# RocketSenseV1.net
KiCad netlist of a schematic drawn in EAGLE
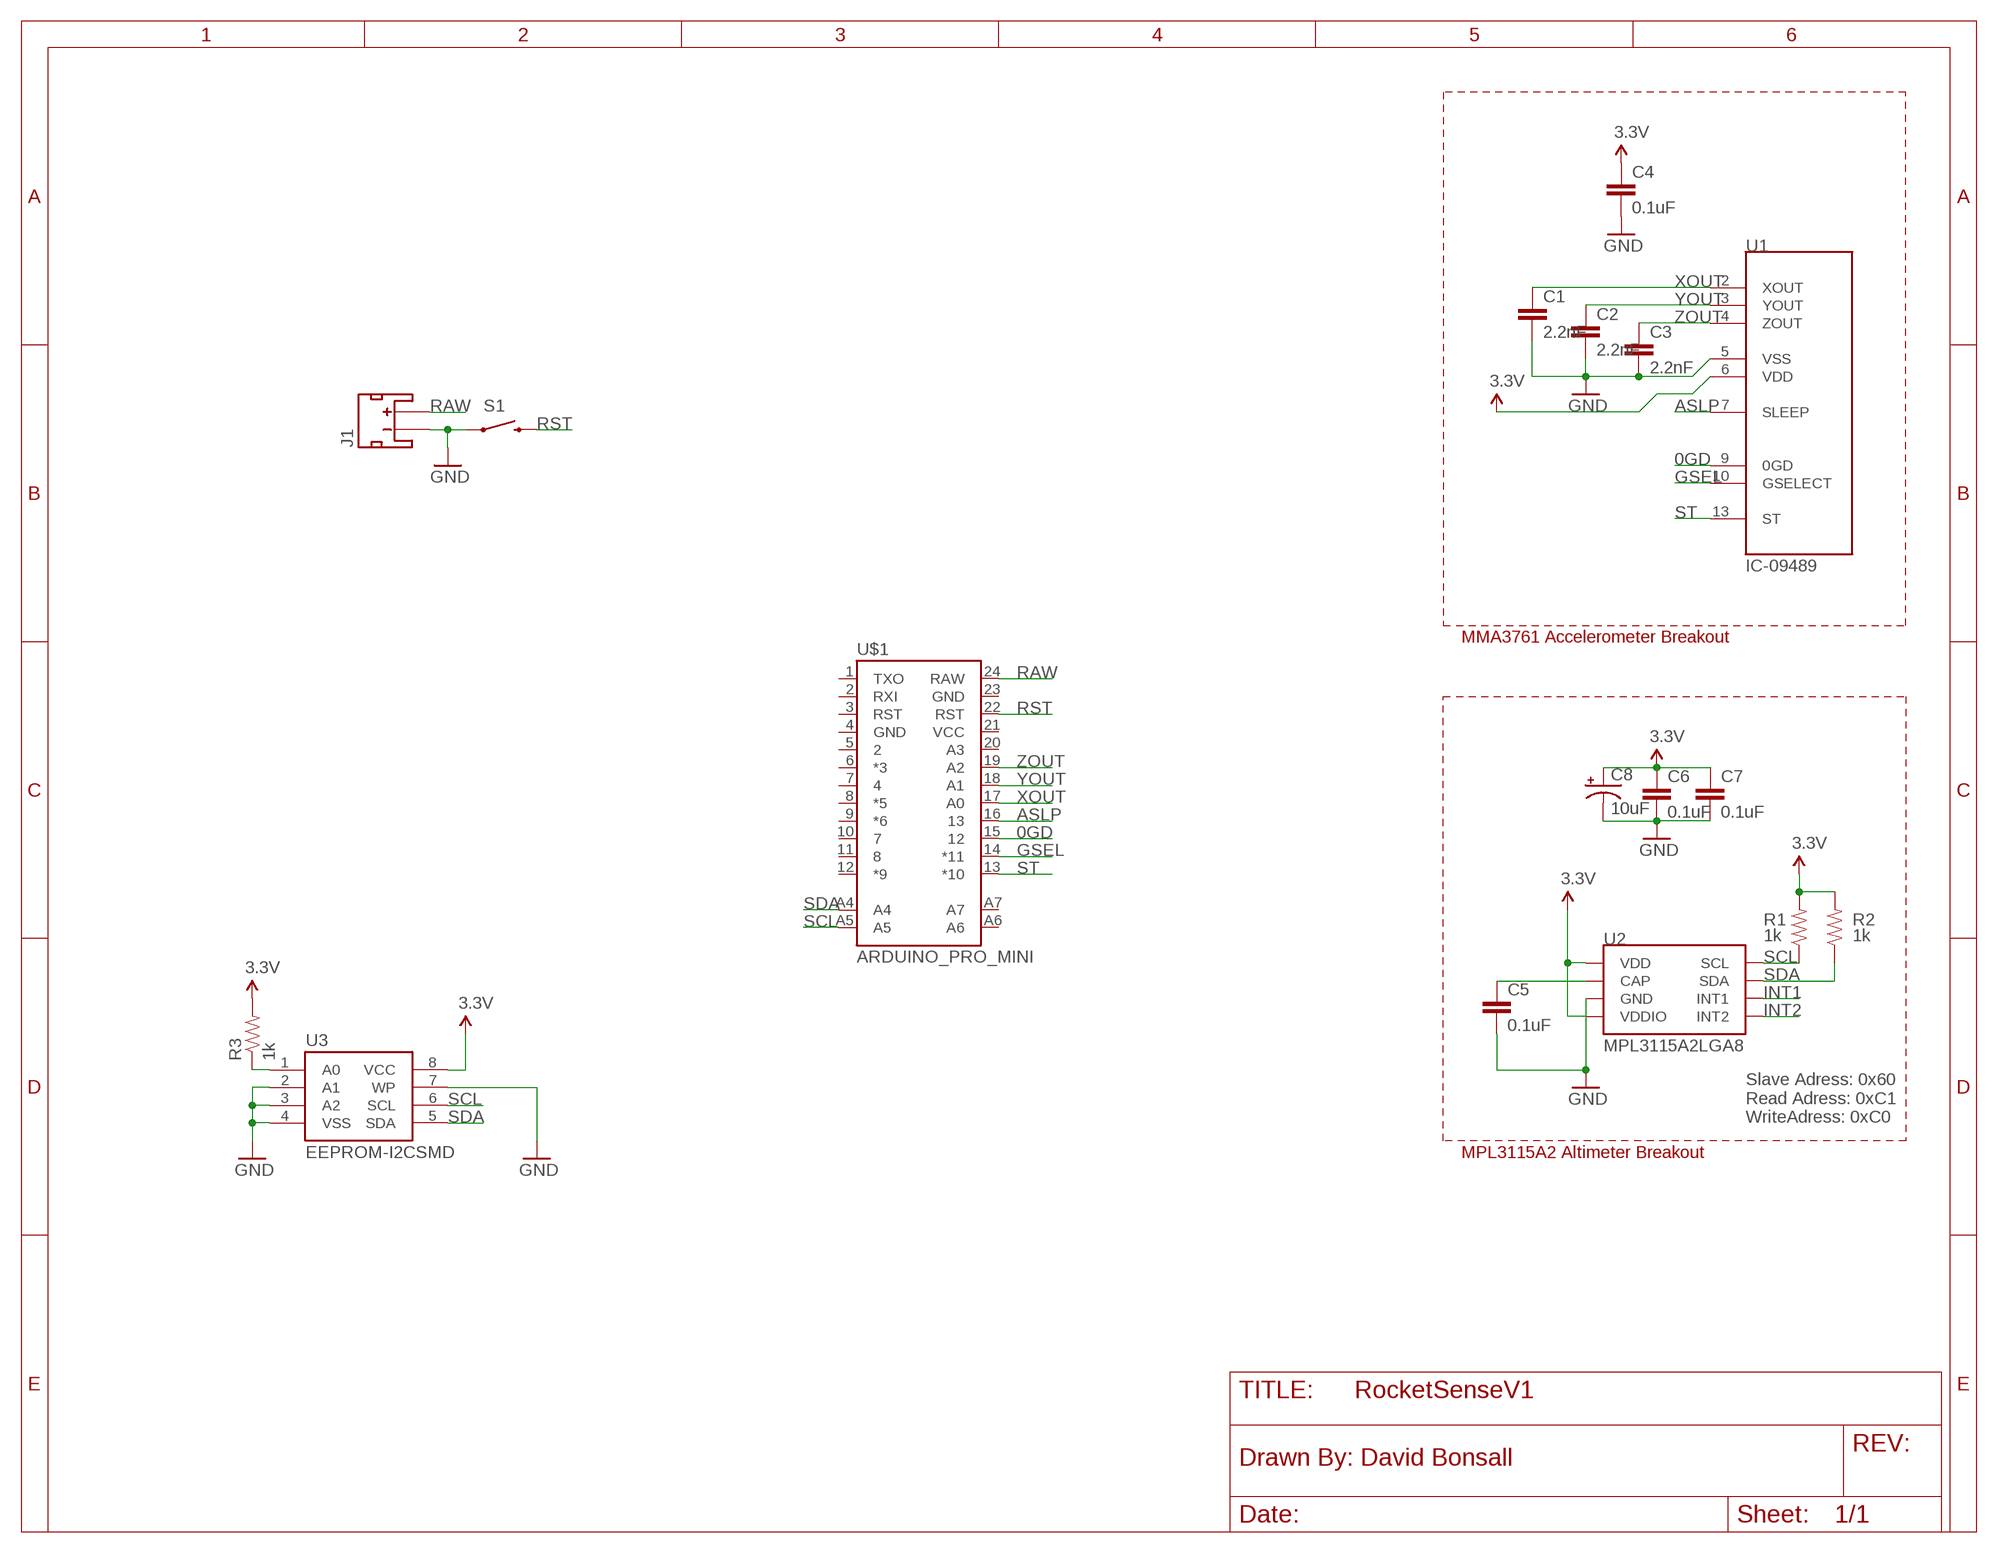
[diagram p0: schematic, sheet 1]

(export (version "E")
  (design (tool "Eeschema 10.0.6"))
  (components
    (comp (ref "C1")
      (value "2.2nF")
      (footprint "eagle-import:0603-CAP")
      (libsource (lib "eagle-import") (part "2.2NF/2200PF-50V-10%(0603)"))
    )
    (comp (ref "C2")
      (value "2.2nF")
      (footprint "eagle-import:0603-CAP")
      (libsource (lib "eagle-import") (part "2.2NF/2200PF-50V-10%(0603)"))
    )
    (comp (ref "C3")
      (value "2.2nF")
      (footprint "eagle-import:0603-CAP")
      (libsource (lib "eagle-import") (part "2.2NF/2200PF-50V-10%(0603)"))
    )
    (comp (ref "C4")
      (value "0.1uF")
      (footprint "eagle-import:0402-CAP")
      (libsource (lib "eagle-import") (part ".1UF-CER"))
    )
    (comp (ref "C5")
      (value "0.1uF")
      (footprint "eagle-import:0402-CAP")
      (libsource (lib "eagle-import") (part ".1UF-CER"))
    )
    (comp (ref "C6")
      (value "0.1uF")
      (footprint "eagle-import:0402-CAP")
      (libsource (lib "eagle-import") (part ".1UF-CER"))
    )
    (comp (ref "C7")
      (value "0.1uF")
      (footprint "eagle-import:0402-CAP")
      (libsource (lib "eagle-import") (part ".1UF-CER"))
    )
    (comp (ref "C8")
      (value "10uF")
      (footprint "eagle-import:EIA3216")
      (libsource (lib "eagle-import") (part "10UF-16V-10%(TANT)"))
    )
    (comp (ref "J1")
      (value "JST_2MM_MALE")
      (footprint "eagle-import:JST-2-SMD")
      (libsource (lib "eagle-import") (part "JST_2MM_MALE"))
    )
    (comp (ref "R1")
      (value "1k")
      (footprint "eagle-import:0603-RES")
      (libsource (lib "eagle-import") (part "1K-1%"))
    )
    (comp (ref "R2")
      (value "1k")
      (footprint "eagle-import:0603-RES")
      (libsource (lib "eagle-import") (part "1K-1%"))
    )
    (comp (ref "R3")
      (value "1k")
      (footprint "eagle-import:0603-RES")
      (libsource (lib "eagle-import") (part "1K-1%"))
    )
    (comp (ref "S1")
      (value "SWITCH-MOMENTARY-2-SMD-1101NE")
      (footprint "eagle-import:TACTILE-SWITCH-1101NE")
      (libsource (lib "eagle-import") (part "SWITCH-MOMENTARY-2-SMD-1101NE"))
    )
    (comp (ref "U$1")
      (value "ARDUINO_PRO_MINI")
      (footprint "eagle-import:ARDUINO_PRO_MINI")
      (libsource (lib "eagle-import") (part "ARDUINO_PRO_MINI"))
    )
    (comp (ref "U1")
      (value "IC-09489")
      (footprint "eagle-import:LGA14")
      (libsource (lib "eagle-import") (part "MMA7361"))
    )
    (comp (ref "U2")
      (value "MPL3115A2LGA8")
      (footprint "eagle-import:LGA8")
      (libsource (lib "eagle-import") (part "MPL3115A2LGA8"))
    )
    (comp (ref "U3")
      (value "EEPROM-I2CSMD")
      (footprint "eagle-import:SO08")
      (libsource (lib "eagle-import") (part "EEPROM-I2CSMD"))
    )
  )
  (nets
    (net (code "1") (name "/0GD") (class "Default")
      (node (ref "U$1") (pin "15") (pinfunction "12_15") (pintype "bidirectional"))
      (node (ref "U1") (pin "9") (pinfunction "0GD_9") (pintype "bidirectional"))
    )
    (net (code "2") (name "/ASLP") (class "Default")
      (node (ref "U$1") (pin "16") (pinfunction "13_16") (pintype "bidirectional"))
      (node (ref "U1") (pin "7") (pinfunction "SLEEP_7") (pintype "bidirectional"))
    )
    (net (code "3") (name "/GSEL") (class "Default")
      (node (ref "U$1") (pin "14") (pinfunction "*11_14") (pintype "bidirectional"))
      (node (ref "U1") (pin "10") (pinfunction "GSELECT_10") (pintype "bidirectional"))
    )
    (net (code "4") (name "/INT1") (class "Default")
      (node (ref "U2") (pin "6") (pinfunction "INT1_6") (pintype "output"))
    )
    (net (code "5") (name "/INT2") (class "Default")
      (node (ref "U2") (pin "5") (pinfunction "INT2_5") (pintype "output"))
    )
    (net (code "6") (name "/RAW") (class "Default")
      (node (ref "J1") (pin "2") (pinfunction "+_2") (pintype "bidirectional"))
      (node (ref "U$1") (pin "24") (pinfunction "RAW_24") (pintype "bidirectional"))
    )
    (net (code "7") (name "/RST") (class "Default")
      (node (ref "S1") (pin "P$2") (pinfunction "2_P$2") (pintype "passive"))
      (node (ref "U$1") (pin "22") (pinfunction "RST_22") (pintype "bidirectional"))
    )
    (net (code "8") (name "/SCL") (class "Default")
      (node (ref "R1") (pin "1") (pinfunction "1_1") (pintype "passive"))
      (node (ref "U$1") (pin "A5") (pinfunction "A5_A5") (pintype "bidirectional"))
      (node (ref "U2") (pin "8") (pinfunction "SCL_8") (pintype "bidirectional"))
      (node (ref "U3") (pin "6") (pinfunction "SCL_6") (pintype "bidirectional"))
    )
    (net (code "9") (name "/SDA") (class "Default")
      (node (ref "R2") (pin "1") (pinfunction "1_1") (pintype "passive"))
      (node (ref "U$1") (pin "A4") (pinfunction "A4_A4") (pintype "bidirectional"))
      (node (ref "U2") (pin "7") (pinfunction "SDA_7") (pintype "bidirectional"))
      (node (ref "U3") (pin "5") (pinfunction "SDA_5") (pintype "bidirectional"))
    )
    (net (code "10") (name "/ST") (class "Default")
      (node (ref "U$1") (pin "13") (pinfunction "*10_13") (pintype "bidirectional"))
      (node (ref "U1") (pin "13") (pinfunction "ST_13") (pintype "bidirectional"))
    )
    (net (code "11") (name "/XOUT") (class "Default")
      (node (ref "C1") (pin "1") (pinfunction "1_1") (pintype "passive"))
      (node (ref "U$1") (pin "17") (pinfunction "A0_17") (pintype "bidirectional"))
      (node (ref "U1") (pin "2") (pinfunction "XOUT_2") (pintype "bidirectional"))
    )
    (net (code "12") (name "/YOUT") (class "Default")
      (node (ref "C2") (pin "1") (pinfunction "1_1") (pintype "passive"))
      (node (ref "U$1") (pin "18") (pinfunction "A1_18") (pintype "bidirectional"))
      (node (ref "U1") (pin "3") (pinfunction "YOUT_3") (pintype "bidirectional"))
    )
    (net (code "13") (name "/ZOUT") (class "Default")
      (node (ref "C3") (pin "1") (pinfunction "1_1") (pintype "passive"))
      (node (ref "U$1") (pin "19") (pinfunction "A2_19") (pintype "bidirectional"))
      (node (ref "U1") (pin "4") (pinfunction "ZOUT_4") (pintype "bidirectional"))
    )
    (net (code "14") (name "3.3V") (class "Default")
      (node (ref "C4") (pin "1") (pinfunction "1_1") (pintype "passive"))
      (node (ref "C6") (pin "1") (pinfunction "1_1") (pintype "passive"))
      (node (ref "C7") (pin "1") (pinfunction "1_1") (pintype "passive"))
      (node (ref "C8") (pin "A") (pinfunction "+_A") (pintype "passive"))
      (node (ref "R1") (pin "2") (pinfunction "2_2") (pintype "passive"))
      (node (ref "R2") (pin "2") (pinfunction "2_2") (pintype "passive"))
      (node (ref "R3") (pin "2") (pinfunction "2_2") (pintype "passive"))
      (node (ref "U1") (pin "6") (pinfunction "VDD_6") (pintype "bidirectional"))
      (node (ref "U2") (pin "1") (pinfunction "VDD_1") (pintype "power_in"))
      (node (ref "U2") (pin "4") (pinfunction "VDDIO_4") (pintype "power_in"))
      (node (ref "U3") (pin "8") (pinfunction "VCC_8") (pintype "power_in"))
    )
    (net (code "15") (name "GND") (class "Default")
      (node (ref "C1") (pin "2") (pinfunction "2_2") (pintype "passive"))
      (node (ref "C2") (pin "2") (pinfunction "2_2") (pintype "passive"))
      (node (ref "C3") (pin "2") (pinfunction "2_2") (pintype "passive"))
      (node (ref "C4") (pin "2") (pinfunction "2_2") (pintype "passive"))
      (node (ref "C5") (pin "2") (pinfunction "2_2") (pintype "passive"))
      (node (ref "C6") (pin "2") (pinfunction "2_2") (pintype "passive"))
      (node (ref "C7") (pin "2") (pinfunction "2_2") (pintype "passive"))
      (node (ref "C8") (pin "C") (pinfunction "-_C") (pintype "passive"))
      (node (ref "J1") (pin "1") (pinfunction "-_1") (pintype "bidirectional"))
      (node (ref "S1") (pin "P$1") (pinfunction "1_P$1") (pintype "passive"))
      (node (ref "U1") (pin "5") (pinfunction "VSS_5") (pintype "bidirectional"))
      (node (ref "U2") (pin "3") (pinfunction "GND_3") (pintype "power_in"))
      (node (ref "U3") (pin "2") (pinfunction "A1_2") (pintype "bidirectional"))
      (node (ref "U3") (pin "3") (pinfunction "A2_3") (pintype "bidirectional"))
      (node (ref "U3") (pin "4") (pinfunction "VSS_4") (pintype "power_in"))
      (node (ref "U3") (pin "7") (pinfunction "WP_7") (pintype "bidirectional"))
    )
    (net (code "16") (name "Net-(U2-CAP)") (class "Default")
      (node (ref "C5") (pin "1") (pinfunction "1_1") (pintype "passive"))
      (node (ref "U2") (pin "2") (pinfunction "CAP_2") (pintype "power_in"))
    )
    (net (code "17") (name "Net-(U3-A0)") (class "Default")
      (node (ref "R3") (pin "1") (pinfunction "1_1") (pintype "passive"))
      (node (ref "U3") (pin "1") (pinfunction "A0_1") (pintype "bidirectional"))
    )
    (net (code "18") (name "unconnected-(J1-PAD1-PadNC1)") (class "Default")
      (node (ref "J1") (pin "NC1") (pinfunction "PAD1_NC1") (pintype "bidirectional"))
    )
    (net (code "19") (name "unconnected-(J1-PAD2-PadNC2)") (class "Default")
      (node (ref "J1") (pin "NC2") (pinfunction "PAD2_NC2") (pintype "bidirectional"))
    )
    (net (code "20") (name "unconnected-(U$1-*3-Pad6)") (class "Default")
      (node (ref "U$1") (pin "6") (pinfunction "*3_6") (pintype "bidirectional"))
    )
    (net (code "21") (name "unconnected-(U$1-*5-Pad8)") (class "Default")
      (node (ref "U$1") (pin "8") (pinfunction "*5_8") (pintype "bidirectional"))
    )
    (net (code "22") (name "unconnected-(U$1-*6-Pad9)") (class "Default")
      (node (ref "U$1") (pin "9") (pinfunction "*6_9") (pintype "bidirectional"))
    )
    (net (code "23") (name "unconnected-(U$1-*9-Pad12)") (class "Default")
      (node (ref "U$1") (pin "12") (pinfunction "*9_12") (pintype "bidirectional"))
    )
    (net (code "24") (name "unconnected-(U$1-2-Pad5)") (class "Default")
      (node (ref "U$1") (pin "5") (pinfunction "2_5") (pintype "bidirectional"))
    )
    (net (code "25") (name "unconnected-(U$1-4-Pad7)") (class "Default")
      (node (ref "U$1") (pin "7") (pinfunction "4_7") (pintype "bidirectional"))
    )
    (net (code "26") (name "unconnected-(U$1-7-Pad10)") (class "Default")
      (node (ref "U$1") (pin "10") (pinfunction "7_10") (pintype "bidirectional"))
    )
    (net (code "27") (name "unconnected-(U$1-8-Pad11)") (class "Default")
      (node (ref "U$1") (pin "11") (pinfunction "8_11") (pintype "bidirectional"))
    )
    (net (code "28") (name "unconnected-(U$1-A3-Pad20)") (class "Default")
      (node (ref "U$1") (pin "20") (pinfunction "A3_20") (pintype "bidirectional"))
    )
    (net (code "29") (name "unconnected-(U$1-GND-Pad4)") (class "Default")
      (node (ref "U$1") (pin "4") (pinfunction "GND_4") (pintype "bidirectional"))
    )
    (net (code "30") (name "unconnected-(U$1-GND-Pad23)") (class "Default")
      (node (ref "U$1") (pin "23") (pinfunction "GND_23") (pintype "bidirectional"))
    )
    (net (code "31") (name "unconnected-(U$1-PadA6)") (class "Default")
      (node (ref "U$1") (pin "A6") (pinfunction "A6_A6") (pintype "bidirectional"))
    )
    (net (code "32") (name "unconnected-(U$1-PadA7)") (class "Default")
      (node (ref "U$1") (pin "A7") (pinfunction "A7_A7") (pintype "bidirectional"))
    )
    (net (code "33") (name "unconnected-(U$1-RST-Pad3)") (class "Default")
      (node (ref "U$1") (pin "3") (pinfunction "RST_3") (pintype "bidirectional"))
    )
    (net (code "34") (name "unconnected-(U$1-RXI-Pad2)") (class "Default")
      (node (ref "U$1") (pin "2") (pinfunction "RXI_2") (pintype "bidirectional"))
    )
    (net (code "35") (name "unconnected-(U$1-TXO-Pad1)") (class "Default")
      (node (ref "U$1") (pin "1") (pinfunction "TXO_1") (pintype "bidirectional"))
    )
    (net (code "36") (name "unconnected-(U$1-VCC-Pad21)") (class "Default")
      (node (ref "U$1") (pin "21") (pinfunction "VCC_21") (pintype "bidirectional"))
    )
  )
)
